# 5_Keys_And_Status.net
KiCad netlist of a schematic drawn in Altium Designer
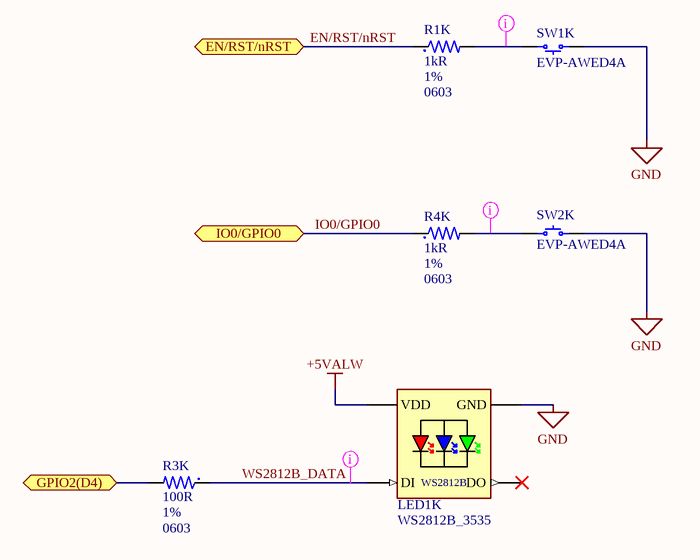
[diagram p0: 5_Keys_And_Status.SchDoc]

(export (version "E")
  (design (tool "Eeschema 10.0.6"))
  (components
    (comp (ref "LED1K")
      (value "WS2812B_3535")
      (footprint "WS2812B-Mini_3535")
      (description "4 PIN SMART LED\r\nWS2812 BODY 3.5MM X 3.5MM")
      (fields (field (name "MP") "WS2812B") (field (name "MF") "SparkFun Electronics"))
      (libsource (lib "Lib_LED") (part "WS2812B_3535"))
    )
    (comp (ref "R1K")
      (value "1kR")
      (footprint "R0603-MFG")
      (description "SMD Chip Resistor, 1 kOhm, ± 1%, 100 mW, 0603 [1608 Metric], Thick Film, General Purpose")
      (fields
        (field (name "MANUFACTURER") "Yageo")
        (field (name "MANUFACTURER PART NUMBER") "RC0603FR-101KL")
        (field (name "TOLERANCE") "1%")
        (field (name "CASE/PACKAGE") "0603")
      )
      (libsource (lib "Lib_Register_0603") (part "1K"))
    )
    (comp (ref "R3K")
      (value "100R")
      (footprint "R0603-MFG")
      (description "SMD Chip Resistor, 100 Ohm, ± 1%, 100 mW, 0603 [1608 Metric], Thick Film, General Purpose")
      (fields
        (field (name "MANUFACTURER") "Yageo")
        (field (name "MANUFACTURER PART NUMBER") "AC0603FR-07100RL")
        (field (name "TOLERANCE") "1%")
        (field (name "CASE/PACKAGE") "0603")
      )
      (libsource (lib "Lib_Register_0603") (part "100R"))
    )
    (comp (ref "R4K")
      (value "1kR")
      (footprint "R0603-MFG")
      (description "SMD Chip Resistor, 1 kOhm, ± 1%, 100 mW, 0603 [1608 Metric], Thick Film, General Purpose")
      (fields
        (field (name "MANUFACTURER") "Yageo")
        (field (name "MANUFACTURER PART NUMBER") "RC0603FR-101KL")
        (field (name "TOLERANCE") "1%")
        (field (name "CASE/PACKAGE") "0603")
      )
      (libsource (lib "Lib_Register_0603") (part "1K"))
    )
    (comp (ref "SW1K")
      (value "EVP-AWED4A")
      (footprint "PANASONIC EVPAW")
      (description "3.0MM X 2.0MM / 3.3N / 0.15MM ST")
      (fields (field (name "MANUFACTURER") "Panasonic Electronic Components"))
      (libsource (lib "Celestial Altium Library - altium_library") (part "SPST-NO 2 PIN"))
    )
    (comp (ref "SW2K")
      (value "EVP-AWED4A")
      (footprint "PANASONIC EVPAW")
      (description "3.0MM X 2.0MM / 3.3N / 0.15MM ST")
      (fields (field (name "MANUFACTURER") "Panasonic Electronic Components"))
      (libsource (lib "Celestial Altium Library - altium_library") (part "SPST-NO 2 PIN"))
    )
  )
  (nets
    (net (code "1") (name "+5VALW") (class "Default")
      (node (ref "LED1K") (pin "1") (pinfunction "VDD_1") (pintype "power_in"))
    )
    (net (code "2") (name "/EN{slash}RST{slash}nRST") (class "Default")
      (node (ref "R1K") (pin "1") (pinfunction "1_1") (pintype "passive"))
    )
    (net (code "3") (name "/GPIO2(D4)") (class "Default")
      (node (ref "R3K") (pin "2") (pinfunction "2_2") (pintype "passive"))
    )
    (net (code "4") (name "/IO0{slash}GPIO0") (class "Default")
      (node (ref "R4K") (pin "1") (pinfunction "1_1") (pintype "passive"))
    )
    (net (code "5") (name "/WS2812B_DATA") (class "Default")
      (node (ref "LED1K") (pin "4") (pinfunction "DI_4") (pintype "input"))
      (node (ref "R3K") (pin "1") (pinfunction "1_1") (pintype "passive"))
    )
    (net (code "6") (name "GND") (class "Default")
      (node (ref "LED1K") (pin "3") (pinfunction "GND_3") (pintype "power_in"))
      (node (ref "SW1K") (pin "1") (pinfunction "1_1") (pintype "passive"))
      (node (ref "SW2K") (pin "2") (pinfunction "2_2") (pintype "passive"))
    )
    (net (code "7") (name "Net-(R1K-Pad2)") (class "Default")
      (node (ref "R1K") (pin "2") (pinfunction "2_2") (pintype "passive"))
      (node (ref "SW1K") (pin "2") (pinfunction "2_2") (pintype "passive"))
    )
    (net (code "8") (name "Net-(R4K-Pad2)") (class "Default")
      (node (ref "R4K") (pin "2") (pinfunction "2_2") (pintype "passive"))
      (node (ref "SW2K") (pin "1") (pinfunction "1_1") (pintype "passive"))
    )
    (net (code "9") (name "unconnected-(LED1K-DO-Pad2)") (class "Default")
      (node (ref "LED1K") (pin "2") (pinfunction "DO_2") (pintype "output+no_connect"))
    )
  )
)
